# Controller_PCB_Base.net
KiCad netlist of a schematic drawn in Altium Designer
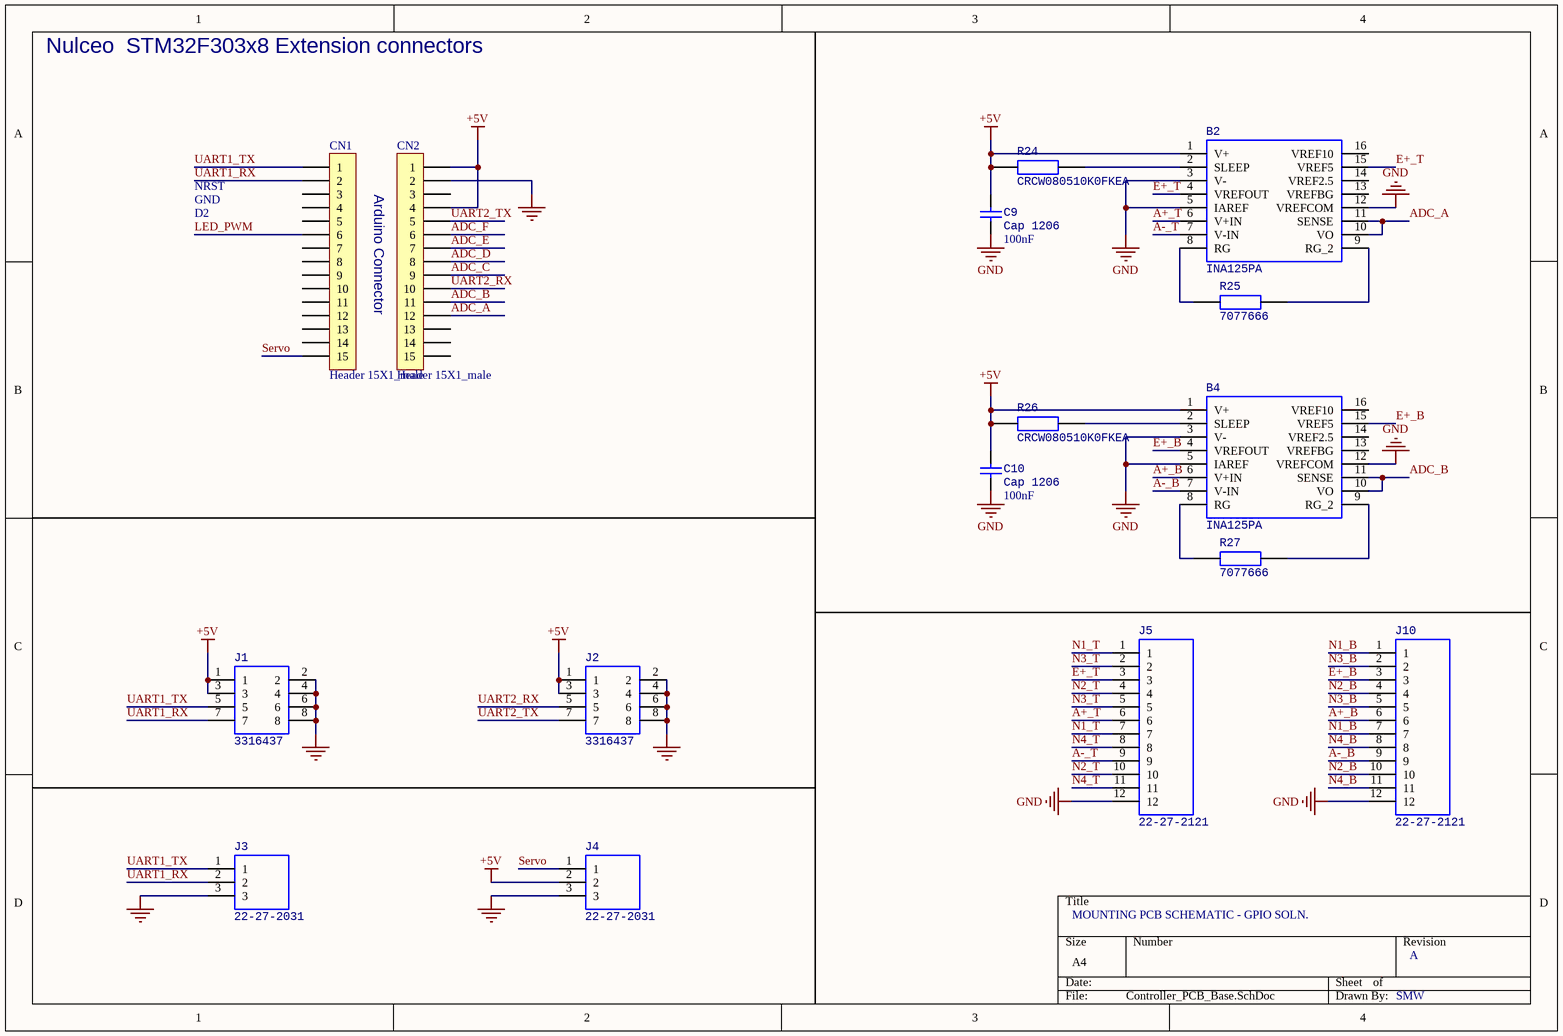
[diagram p0: Controller_PCB_Base.SchDoc]

(export (version "E")
  (design (tool "Eeschema 10.0.6"))
  (components
    (comp (ref "B2")
      (value "INA125PA")
      (footprint "DIP254P762X508-16")
      (description "Instrumentation Amplifier with Precision Voltage Reference")
      (fields (field (name "RS PART NUMBER") "2521593P"))
      (libsource (lib "INA125PA") (part "INA125PA"))
    )
    (comp (ref "B4")
      (value "INA125PA")
      (footprint "DIP254P762X508-16")
      (description "Instrumentation Amplifier with Precision Voltage Reference")
      (fields (field (name "RS PART NUMBER") "2521593P"))
      (libsource (lib "INA125PA") (part "INA125PA"))
    )
    (comp (ref "C9")
      (value "Cap 1206")
      (footprint "C1206")
      (description "Capacitor (Semiconductor SIM Model)")
      (fields (field (name "ALTIUM_VALUE") "100nF") (field (name "PUBLISHER") "Altium Limited"))
      (libsource (lib "Miscellaneous Devices") (part "Cap Semi"))
    )
    (comp (ref "C10")
      (value "Cap 1206")
      (footprint "C1206")
      (description "Capacitor (Semiconductor SIM Model)")
      (fields (field (name "ALTIUM_VALUE") "100nF") (field (name "PUBLISHER") "Altium Limited"))
      (libsource (lib "Miscellaneous Devices") (part "Cap Semi"))
    )
    (comp (ref "CN1")
      (value "Header 15X1_male")
      (footprint "HDR_1x15_2R54_V_F")
      (description "Header, 10-Pin, Single row,female")
      (fields (field (name "PUBLISHER") "Altium Limited"))
      (libsource (lib "") (part "Header 15X1_Female_1_1"))
    )
    (comp (ref "CN2")
      (value "Header 15X1_male")
      (footprint "HDR_1x15_2R54_V_F")
      (description "Header, 10-Pin, Single row,female")
      (fields (field (name "PUBLISHER") "Altium Limited"))
      (libsource (lib "MB1180") (part "Header 15X1_Female_1"))
    )
    (comp (ref "J1") (value "3316437") (footprint "RJ45-8") (libsource (lib "3316437") (part "3316437")))
    (comp (ref "J2") (value "3316437") (footprint "RJ45-8") (libsource (lib "3316437") (part "3316437")))
    (comp (ref "J3")
      (value "22-27-2031")
      (footprint "SHDR3W64P0X254_1X3_762X580X1170P")
      (fields (field (name "RS PART NUMBER") "1707102"))
      (libsource (lib "22-27-2031") (part "22-27-2031"))
    )
    (comp (ref "J4")
      (value "22-27-2031")
      (footprint "SHDR3W64P0X254_1X3_762X580X1170P")
      (fields (field (name "RS PART NUMBER") "1707102"))
      (libsource (lib "22-27-2031") (part "22-27-2031"))
    )
    (comp (ref "J5")
      (value "22-27-2121")
      (footprint "HDRV12W64P0X254_1X12_3048X580X1170P")
      (fields (field (name "RS PART NUMBER") "1707108"))
      (libsource (lib "22-27-2121") (part "22-27-2121"))
    )
    (comp (ref "J10")
      (value "22-27-2121")
      (footprint "HDRV12W64P0X254_1X12_3048X580X1170P")
      (fields (field (name "RS PART NUMBER") "1707108"))
      (libsource (lib "22-27-2121") (part "22-27-2121"))
    )
    (comp (ref "R24")
      (value "CRCW080510K0FKEA")
      (footprint "RESC2012X50N")
      (fields (field (name "RS PART NUMBER") "1694499"))
      (libsource (lib "CRCW080510K0FKEA") (part "CRCW080510K0FKEA"))
    )
    (comp (ref "R25")
      (value "7077666")
      (footprint "RESAD1550W58L630D230")
      (description "RS Pro RS Series Axial Carbon Resistor 1k 5% 0.25W -500  +350ppm/C")
      (libsource (lib "7077666") (part "7077666"))
    )
    (comp (ref "R26")
      (value "CRCW080510K0FKEA")
      (footprint "RESC2012X50N")
      (fields (field (name "RS PART NUMBER") "1694499"))
      (libsource (lib "CRCW080510K0FKEA") (part "CRCW080510K0FKEA"))
    )
    (comp (ref "R27")
      (value "7077666")
      (footprint "RESAD1550W58L630D230")
      (description "RS Pro RS Series Axial Carbon Resistor 1k 5% 0.25W -500  +350ppm/C")
      (libsource (lib "7077666") (part "7077666"))
    )
  )
  (nets
    (net (code "1") (name "+5V") (class "Default")
      (node (ref "B2") (pin "1") (pinfunction "V+_1") (pintype "passive"))
      (node (ref "B4") (pin "1") (pinfunction "V+_1") (pintype "passive"))
      (node (ref "C10") (pin "2") (pinfunction "2_2") (pintype "passive"))
      (node (ref "C9") (pin "2") (pinfunction "2_2") (pintype "passive"))
      (node (ref "CN2") (pin "1") (pinfunction "1_1") (pintype "passive"))
      (node (ref "CN2") (pin "4") (pinfunction "4_4") (pintype "passive"))
      (node (ref "J1") (pin "1") (pinfunction "1_1") (pintype "passive"))
      (node (ref "J1") (pin "3") (pinfunction "3_3") (pintype "passive"))
      (node (ref "J2") (pin "1") (pinfunction "1_1") (pintype "passive"))
      (node (ref "J2") (pin "3") (pinfunction "3_3") (pintype "passive"))
      (node (ref "J4") (pin "2") (pinfunction "2_2") (pintype "passive"))
      (node (ref "R24") (pin "1") (pinfunction "1_1") (pintype "passive"))
      (node (ref "R26") (pin "1") (pinfunction "1_1") (pintype "passive"))
    )
    (net (code "2") (name "/A+_B") (class "Default")
      (node (ref "B4") (pin "6") (pinfunction "V+IN_6") (pintype "passive"))
      (node (ref "J10") (pin "6") (pinfunction "6_6") (pintype "passive"))
    )
    (net (code "3") (name "/A+_T") (class "Default")
      (node (ref "B2") (pin "6") (pinfunction "V+IN_6") (pintype "passive"))
      (node (ref "J5") (pin "6") (pinfunction "6_6") (pintype "passive"))
    )
    (net (code "4") (name "/A-_B") (class "Default")
      (node (ref "B4") (pin "7") (pinfunction "V-IN_7") (pintype "passive"))
      (node (ref "J10") (pin "9") (pinfunction "9_9") (pintype "passive"))
    )
    (net (code "5") (name "/A-_T") (class "Default")
      (node (ref "B2") (pin "7") (pinfunction "V-IN_7") (pintype "passive"))
      (node (ref "J5") (pin "9") (pinfunction "9_9") (pintype "passive"))
    )
    (net (code "6") (name "/ADC_A") (class "Default")
      (node (ref "B2") (pin "10") (pinfunction "VO_10") (pintype "passive"))
      (node (ref "B2") (pin "11") (pinfunction "SENSE_11") (pintype "passive"))
      (node (ref "CN2") (pin "12") (pinfunction "12_12") (pintype "passive"))
    )
    (net (code "7") (name "/ADC_B") (class "Default")
      (node (ref "B4") (pin "10") (pinfunction "VO_10") (pintype "passive"))
      (node (ref "B4") (pin "11") (pinfunction "SENSE_11") (pintype "passive"))
      (node (ref "CN2") (pin "11") (pinfunction "11_11") (pintype "passive"))
    )
    (net (code "8") (name "/ADC_C") (class "Default")
      (node (ref "CN2") (pin "9") (pinfunction "9_9") (pintype "passive"))
    )
    (net (code "9") (name "/ADC_D") (class "Default")
      (node (ref "CN2") (pin "8") (pinfunction "8_8") (pintype "passive"))
    )
    (net (code "10") (name "/ADC_E") (class "Default")
      (node (ref "CN2") (pin "7") (pinfunction "7_7") (pintype "passive"))
    )
    (net (code "11") (name "/ADC_F") (class "Default")
      (node (ref "CN2") (pin "6") (pinfunction "6_6") (pintype "passive"))
    )
    (net (code "12") (name "/E+_B") (class "Default")
      (node (ref "B4") (pin "15") (pinfunction "VREF5_15") (pintype "passive"))
      (node (ref "B4") (pin "4") (pinfunction "VREFOUT_4") (pintype "passive"))
      (node (ref "J10") (pin "3") (pinfunction "3_3") (pintype "passive"))
    )
    (net (code "13") (name "/E+_T") (class "Default")
      (node (ref "B2") (pin "15") (pinfunction "VREF5_15") (pintype "passive"))
      (node (ref "B2") (pin "4") (pinfunction "VREFOUT_4") (pintype "passive"))
      (node (ref "J5") (pin "3") (pinfunction "3_3") (pintype "passive"))
    )
    (net (code "14") (name "/LED_PWM") (class "Default")
      (node (ref "CN1") (pin "6") (pinfunction "6_6") (pintype "passive"))
    )
    (net (code "15") (name "/N1_B") (class "Default")
      (node (ref "J10") (pin "1") (pinfunction "1_1") (pintype "passive"))
      (node (ref "J10") (pin "7") (pinfunction "7_7") (pintype "passive"))
    )
    (net (code "16") (name "/N1_T") (class "Default")
      (node (ref "J5") (pin "1") (pinfunction "1_1") (pintype "passive"))
      (node (ref "J5") (pin "7") (pinfunction "7_7") (pintype "passive"))
    )
    (net (code "17") (name "/N2_B") (class "Default")
      (node (ref "J10") (pin "10") (pinfunction "10_10") (pintype "passive"))
      (node (ref "J10") (pin "4") (pinfunction "4_4") (pintype "passive"))
    )
    (net (code "18") (name "/N2_T") (class "Default")
      (node (ref "J5") (pin "10") (pinfunction "10_10") (pintype "passive"))
      (node (ref "J5") (pin "4") (pinfunction "4_4") (pintype "passive"))
    )
    (net (code "19") (name "/N3_B") (class "Default")
      (node (ref "J10") (pin "2") (pinfunction "2_2") (pintype "passive"))
      (node (ref "J10") (pin "5") (pinfunction "5_5") (pintype "passive"))
    )
    (net (code "20") (name "/N3_T") (class "Default")
      (node (ref "J5") (pin "2") (pinfunction "2_2") (pintype "passive"))
      (node (ref "J5") (pin "5") (pinfunction "5_5") (pintype "passive"))
    )
    (net (code "21") (name "/N4_B") (class "Default")
      (node (ref "J10") (pin "11") (pinfunction "11_11") (pintype "passive"))
      (node (ref "J10") (pin "8") (pinfunction "8_8") (pintype "passive"))
    )
    (net (code "22") (name "/N4_T") (class "Default")
      (node (ref "J5") (pin "11") (pinfunction "11_11") (pintype "passive"))
      (node (ref "J5") (pin "8") (pinfunction "8_8") (pintype "passive"))
    )
    (net (code "23") (name "/Servo") (class "Default")
      (node (ref "CN1") (pin "15") (pinfunction "15_15") (pintype "passive"))
      (node (ref "J4") (pin "1") (pinfunction "1_1") (pintype "passive"))
    )
    (net (code "24") (name "/UART1_RX") (class "Default")
      (node (ref "CN1") (pin "2") (pinfunction "2_2") (pintype "passive"))
      (node (ref "J1") (pin "7") (pinfunction "7_7") (pintype "passive"))
      (node (ref "J3") (pin "2") (pinfunction "2_2") (pintype "passive"))
    )
    (net (code "25") (name "/UART1_TX") (class "Default")
      (node (ref "CN1") (pin "1") (pinfunction "1_1") (pintype "passive"))
      (node (ref "J1") (pin "5") (pinfunction "5_5") (pintype "passive"))
      (node (ref "J3") (pin "1") (pinfunction "1_1") (pintype "passive"))
    )
    (net (code "26") (name "/UART2_RX") (class "Default")
      (node (ref "CN2") (pin "10") (pinfunction "10_10") (pintype "passive"))
      (node (ref "J2") (pin "5") (pinfunction "5_5") (pintype "passive"))
    )
    (net (code "27") (name "/UART2_TX") (class "Default")
      (node (ref "CN2") (pin "5") (pinfunction "5_5") (pintype "passive"))
      (node (ref "J2") (pin "7") (pinfunction "7_7") (pintype "passive"))
    )
    (net (code "28") (name "GND") (class "Default")
      (node (ref "B2") (pin "12") (pinfunction "VREFCOM_12") (pintype "passive"))
      (node (ref "B2") (pin "3") (pinfunction "V-_3") (pintype "passive"))
      (node (ref "B2") (pin "5") (pinfunction "IAREF_5") (pintype "passive"))
      (node (ref "B4") (pin "12") (pinfunction "VREFCOM_12") (pintype "passive"))
      (node (ref "B4") (pin "3") (pinfunction "V-_3") (pintype "passive"))
      (node (ref "B4") (pin "5") (pinfunction "IAREF_5") (pintype "passive"))
      (node (ref "C10") (pin "1") (pinfunction "1_1") (pintype "passive"))
      (node (ref "C9") (pin "1") (pinfunction "1_1") (pintype "passive"))
      (node (ref "CN2") (pin "2") (pinfunction "2_2") (pintype "passive"))
      (node (ref "J1") (pin "2") (pinfunction "2_2") (pintype "passive"))
      (node (ref "J1") (pin "4") (pinfunction "4_4") (pintype "passive"))
      (node (ref "J1") (pin "6") (pinfunction "6_6") (pintype "passive"))
      (node (ref "J1") (pin "8") (pinfunction "8_8") (pintype "passive"))
      (node (ref "J10") (pin "12") (pinfunction "12_12") (pintype "passive"))
      (node (ref "J2") (pin "2") (pinfunction "2_2") (pintype "passive"))
      (node (ref "J2") (pin "4") (pinfunction "4_4") (pintype "passive"))
      (node (ref "J2") (pin "6") (pinfunction "6_6") (pintype "passive"))
      (node (ref "J2") (pin "8") (pinfunction "8_8") (pintype "passive"))
      (node (ref "J3") (pin "3") (pinfunction "3_3") (pintype "passive"))
      (node (ref "J4") (pin "3") (pinfunction "3_3") (pintype "passive"))
      (node (ref "J5") (pin "12") (pinfunction "12_12") (pintype "passive"))
    )
    (net (code "29") (name "Net-(B2-RG)") (class "Default")
      (node (ref "B2") (pin "8") (pinfunction "RG_8") (pintype "passive"))
      (node (ref "R25") (pin "1") (pinfunction "1_1") (pintype "passive"))
    )
    (net (code "30") (name "Net-(B2-RG_2)") (class "Default")
      (node (ref "B2") (pin "9") (pinfunction "RG_2_9") (pintype "passive"))
      (node (ref "R25") (pin "2") (pinfunction "2_2") (pintype "passive"))
    )
    (net (code "31") (name "Net-(B2-SLEEP)") (class "Default")
      (node (ref "B2") (pin "2") (pinfunction "SLEEP_2") (pintype "passive"))
      (node (ref "R24") (pin "2") (pinfunction "2_2") (pintype "passive"))
    )
    (net (code "32") (name "Net-(B4-RG)") (class "Default")
      (node (ref "B4") (pin "8") (pinfunction "RG_8") (pintype "passive"))
      (node (ref "R27") (pin "1") (pinfunction "1_1") (pintype "passive"))
    )
    (net (code "33") (name "Net-(B4-RG_2)") (class "Default")
      (node (ref "B4") (pin "9") (pinfunction "RG_2_9") (pintype "passive"))
      (node (ref "R27") (pin "2") (pinfunction "2_2") (pintype "passive"))
    )
    (net (code "34") (name "Net-(B4-SLEEP)") (class "Default")
      (node (ref "B4") (pin "2") (pinfunction "SLEEP_2") (pintype "passive"))
      (node (ref "R26") (pin "2") (pinfunction "2_2") (pintype "passive"))
    )
    (net (code "35") (name "unconnected-(B2-VREF2.5-Pad14)") (class "Default")
      (node (ref "B2") (pin "14") (pinfunction "VREF2.5_14") (pintype "passive"))
    )
    (net (code "36") (name "unconnected-(B2-VREF10-Pad16)") (class "Default")
      (node (ref "B2") (pin "16") (pinfunction "VREF10_16") (pintype "passive"))
    )
    (net (code "37") (name "unconnected-(B2-VREFBG-Pad13)") (class "Default")
      (node (ref "B2") (pin "13") (pinfunction "VREFBG_13") (pintype "passive"))
    )
    (net (code "38") (name "unconnected-(B4-VREF2.5-Pad14)") (class "Default")
      (node (ref "B4") (pin "14") (pinfunction "VREF2.5_14") (pintype "passive"))
    )
    (net (code "39") (name "unconnected-(B4-VREF10-Pad16)") (class "Default")
      (node (ref "B4") (pin "16") (pinfunction "VREF10_16") (pintype "passive"))
    )
    (net (code "40") (name "unconnected-(B4-VREFBG-Pad13)") (class "Default")
      (node (ref "B4") (pin "13") (pinfunction "VREFBG_13") (pintype "passive"))
    )
    (net (code "41") (name "unconnected-(CN1-Pad3)") (class "Default")
      (node (ref "CN1") (pin "3") (pinfunction "3_3") (pintype "passive"))
    )
    (net (code "42") (name "unconnected-(CN1-Pad4)") (class "Default")
      (node (ref "CN1") (pin "4") (pinfunction "4_4") (pintype "passive"))
    )
    (net (code "43") (name "unconnected-(CN1-Pad5)") (class "Default")
      (node (ref "CN1") (pin "5") (pinfunction "5_5") (pintype "passive"))
    )
    (net (code "44") (name "unconnected-(CN1-Pad7)") (class "Default")
      (node (ref "CN1") (pin "7") (pinfunction "7_7") (pintype "passive"))
    )
    (net (code "45") (name "unconnected-(CN1-Pad8)") (class "Default")
      (node (ref "CN1") (pin "8") (pinfunction "8_8") (pintype "passive"))
    )
    (net (code "46") (name "unconnected-(CN1-Pad9)") (class "Default")
      (node (ref "CN1") (pin "9") (pinfunction "9_9") (pintype "passive"))
    )
    (net (code "47") (name "unconnected-(CN1-Pad10)") (class "Default")
      (node (ref "CN1") (pin "10") (pinfunction "10_10") (pintype "passive"))
    )
    (net (code "48") (name "unconnected-(CN1-Pad11)") (class "Default")
      (node (ref "CN1") (pin "11") (pinfunction "11_11") (pintype "passive"))
    )
    (net (code "49") (name "unconnected-(CN1-Pad12)") (class "Default")
      (node (ref "CN1") (pin "12") (pinfunction "12_12") (pintype "passive"))
    )
    (net (code "50") (name "unconnected-(CN1-Pad13)") (class "Default")
      (node (ref "CN1") (pin "13") (pinfunction "13_13") (pintype "passive"))
    )
    (net (code "51") (name "unconnected-(CN1-Pad14)") (class "Default")
      (node (ref "CN1") (pin "14") (pinfunction "14_14") (pintype "passive"))
    )
    (net (code "52") (name "unconnected-(CN2-Pad3)") (class "Default")
      (node (ref "CN2") (pin "3") (pinfunction "3_3") (pintype "passive"))
    )
    (net (code "53") (name "unconnected-(CN2-Pad13)") (class "Default")
      (node (ref "CN2") (pin "13") (pinfunction "13_13") (pintype "passive"))
    )
    (net (code "54") (name "unconnected-(CN2-Pad14)") (class "Default")
      (node (ref "CN2") (pin "14") (pinfunction "14_14") (pintype "passive"))
    )
    (net (code "55") (name "unconnected-(CN2-Pad15)") (class "Default")
      (node (ref "CN2") (pin "15") (pinfunction "15_15") (pintype "passive"))
    )
  )
)
